# cyrf6936-bob.net
KiCad netlist of a schematic drawn in EAGLE
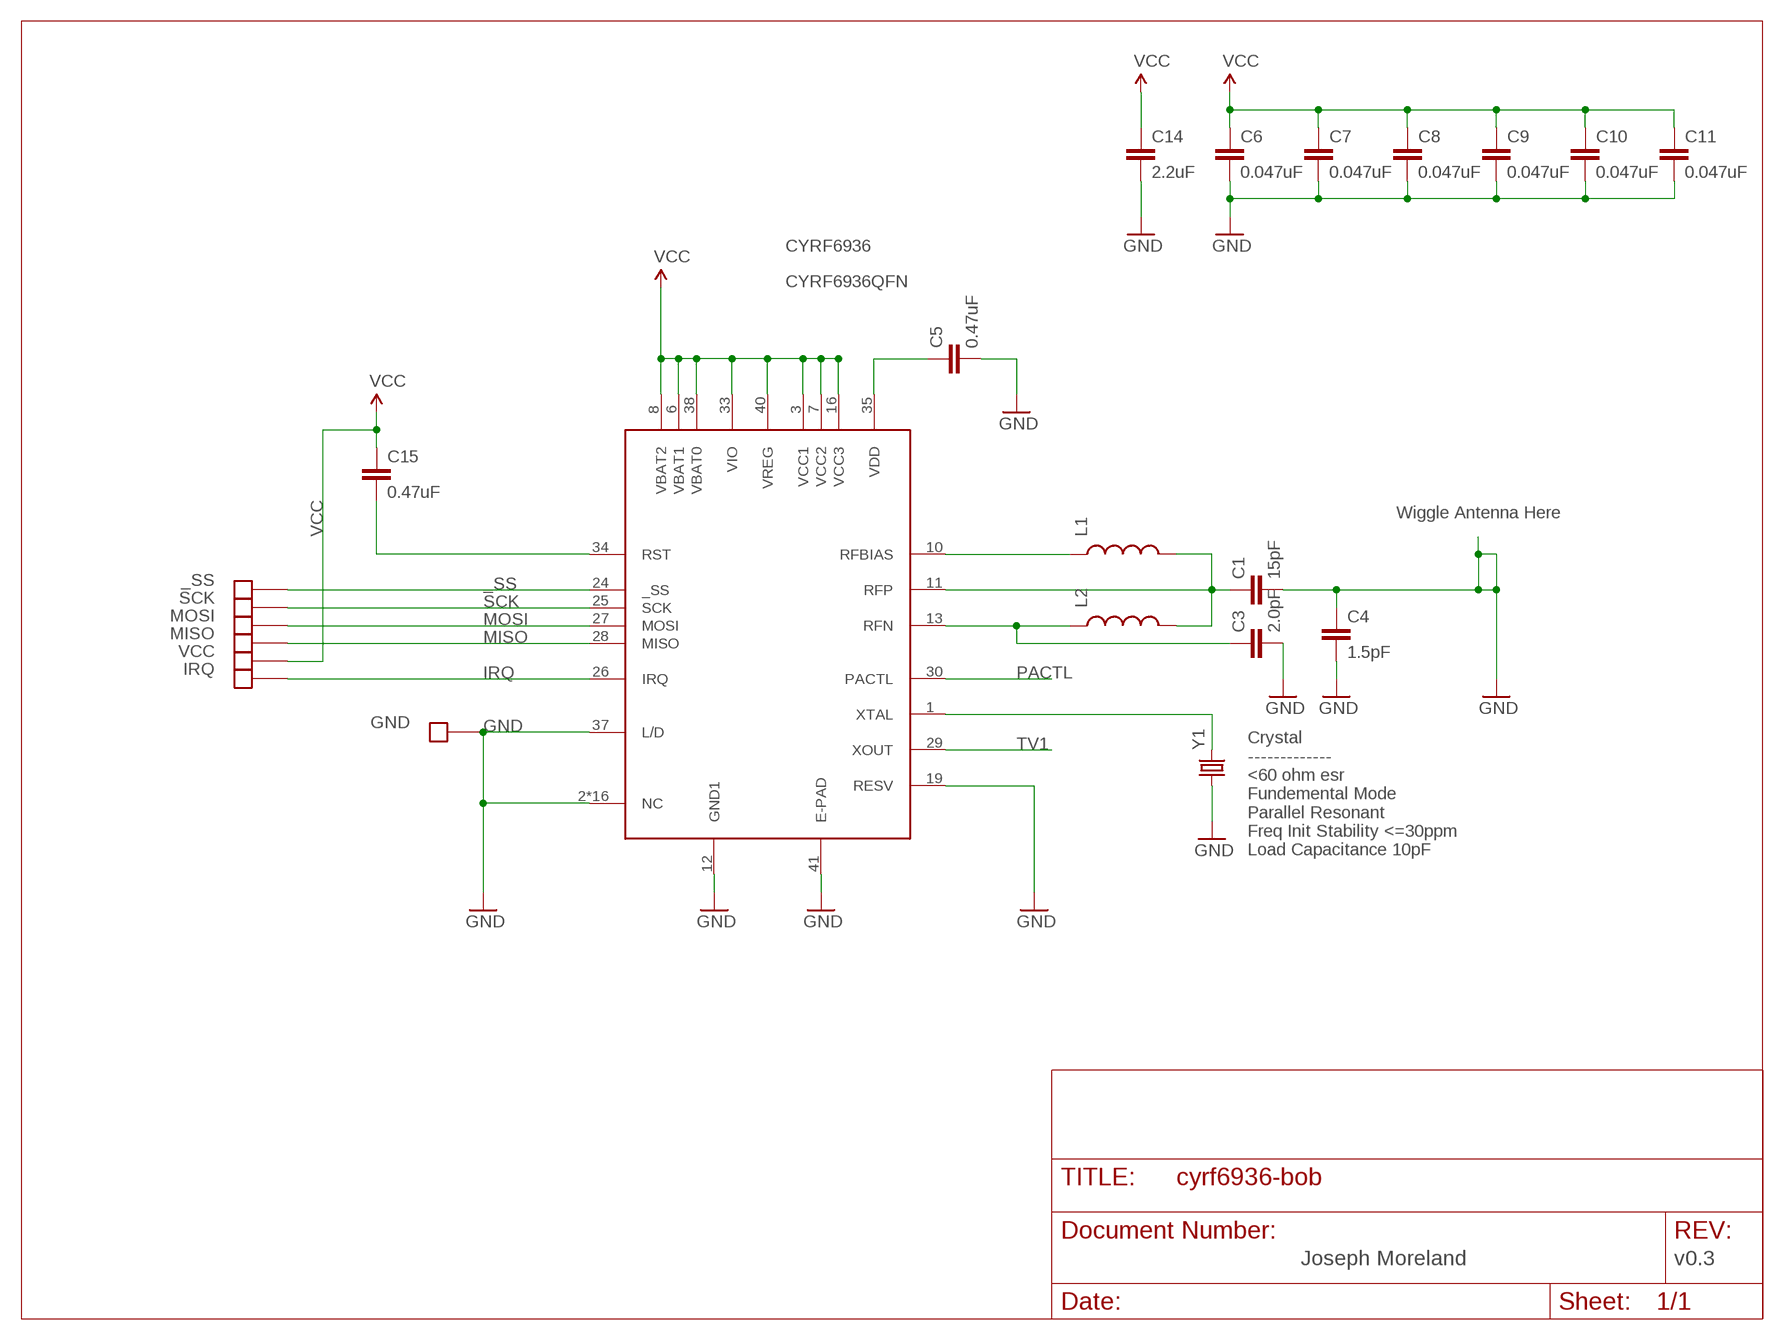
[diagram p0: schematic, sheet 1]

(export (version "E")
  (design (tool "Eeschema 10.0.6"))
  (components
    (comp (ref "C1")
      (value "15pF")
      (footprint "eagle-import:0402-CAP")
      (fields (field (name "PARTNO") "C0402C150J5GACTU"))
      (libsource (lib "eagle-import") (part "CAP0402-CAP"))
    )
    (comp (ref "C3")
      (value "2.0pF")
      (footprint "eagle-import:0402-CAP")
      (fields (field (name "PARTNO") "C0402C209C5GACTU"))
      (libsource (lib "eagle-import") (part "CAP0402-CAP"))
    )
    (comp (ref "C4")
      (value "1.5pF")
      (footprint "eagle-import:0402-CAP")
      (fields (field (name "PARTNO") "C0402C159B5GACTU"))
      (libsource (lib "eagle-import") (part "CAP0402-CAP"))
    )
    (comp (ref "C5")
      (value "0.47uF")
      (footprint "eagle-import:0402-CAP")
      (fields (field (name "PARTNO") "GRM155R60J474KE19D"))
      (libsource (lib "eagle-import") (part "CAP0402-CAP"))
    )
    (comp (ref "C6")
      (value "0.047uF")
      (footprint "eagle-import:0402-CAP")
      (fields (field (name "PARTNO") "0402YD473KAT2A"))
      (libsource (lib "eagle-import") (part "CAP0402-CAP"))
    )
    (comp (ref "C7")
      (value "0.047uF")
      (footprint "eagle-import:0402-CAP")
      (fields (field (name "PARTNO") "0402YD473KAT2A"))
      (libsource (lib "eagle-import") (part "CAP0402-CAP"))
    )
    (comp (ref "C8")
      (value "0.047uF")
      (footprint "eagle-import:0402-CAP")
      (fields (field (name "PARTNO") "0402YD473KAT2A"))
      (libsource (lib "eagle-import") (part "CAP0402-CAP"))
    )
    (comp (ref "C9")
      (value "0.047uF")
      (footprint "eagle-import:0402-CAP")
      (fields (field (name "PARTNO") "0402YD473KAT2A"))
      (libsource (lib "eagle-import") (part "CAP0402-CAP"))
    )
    (comp (ref "C10")
      (value "0.047uF")
      (footprint "eagle-import:0402-CAP")
      (fields (field (name "PARTNO") "0402YD473KAT2A"))
      (libsource (lib "eagle-import") (part "CAP0402-CAP"))
    )
    (comp (ref "C11")
      (value "0.047uF")
      (footprint "eagle-import:0402-CAP")
      (fields (field (name "PARTNO") "0402YD473KAT2A"))
      (libsource (lib "eagle-import") (part "CAP0402-CAP"))
    )
    (comp (ref "C14")
      (value "2.2uF")
      (footprint "eagle-import:0805")
      (fields (field (name "PARTNO") "GRM21BR71A225KA01L"))
      (libsource (lib "eagle-import") (part "CAP0805"))
    )
    (comp (ref "C15")
      (value "0.47uF")
      (footprint "eagle-import:0402-CAP")
      (fields (field (name "PARTNO") "GRM155R60J474KE19D"))
      (libsource (lib "eagle-import") (part "CAP0402-CAP"))
    )
    (comp (ref "CYRF6936")
      (value "CYRF6936QFN")
      (footprint "eagle-import:QFN50P600X600X90-41N")
      (fields (field (name "PARTNO") "CYRF6936B-40LTXC"))
      (libsource (lib "eagle-import") (part "CYRF6936QFN"))
    )
    (comp (ref "GND")
      (value "SOLDER_PADTH")
      (footprint "eagle-import:1X1_50MIL")
      (libsource (lib "eagle-import") (part "SOLDER_PADTH"))
    )
    (comp (ref "IRQ")
      (value "SOLDER_PADTH")
      (footprint "eagle-import:1X1_50MIL")
      (libsource (lib "eagle-import") (part "SOLDER_PADTH"))
    )
    (comp (ref "L1")
      (value "INDUCTOR0603")
      (footprint "eagle-import:0603")
      (fields (field (name "PARTNO") "ELJ-RE22NGFA"))
      (libsource (lib "eagle-import") (part "INDUCTOR0603"))
    )
    (comp (ref "L2")
      (value "INDUCTOR0402")
      (footprint "eagle-import:C0402")
      (fields (field (name "PARTNO") "ELJ-RF1N8DFB"))
      (libsource (lib "eagle-import") (part "INDUCTOR0402"))
    )
    (comp (ref "MISO")
      (value "SOLDER_PADTH")
      (footprint "eagle-import:1X1_50MIL")
      (libsource (lib "eagle-import") (part "SOLDER_PADTH"))
    )
    (comp (ref "MOSI")
      (value "SOLDER_PADTH")
      (footprint "eagle-import:1X1_50MIL")
      (libsource (lib "eagle-import") (part "SOLDER_PADTH"))
    )
    (comp (ref "SCK")
      (value "SOLDER_PADTH")
      (footprint "eagle-import:1X1_50MIL")
      (libsource (lib "eagle-import") (part "SOLDER_PADTH"))
    )
    (comp (ref "VCC")
      (value "SOLDER_PADTH")
      (footprint "eagle-import:1X1_50MIL")
      (libsource (lib "eagle-import") (part "SOLDER_PADTH"))
    )
    (comp (ref "Y1")
      (value "CRYSTAL5X3")
      (footprint "eagle-import:CRYSTAL-SMD-5X3")
      (fields (field (name "PARTNO") "7B-12.000MEEQ-T"))
      (libsource (lib "eagle-import") (part "CRYSTAL5X3"))
    )
    (comp (ref "_SS")
      (value "SOLDER_PADTH")
      (footprint "eagle-import:1X1_50MIL")
      (libsource (lib "eagle-import") (part "SOLDER_PADTH"))
    )
  )
  (nets
    (net (code "1") (name "/IRQ") (class "Default")
      (node (ref "CYRF6936") (pin "26") (pinfunction "IRQ_26") (pintype "bidirectional"))
      (node (ref "IRQ") (pin "P$1") (pinfunction "NET_P$1") (pintype "bidirectional"))
    )
    (net (code "2") (name "/MISO") (class "Default")
      (node (ref "CYRF6936") (pin "28") (pinfunction "MISO_28") (pintype "bidirectional"))
      (node (ref "MISO") (pin "P$1") (pinfunction "NET_P$1") (pintype "bidirectional"))
    )
    (net (code "3") (name "/MOSI") (class "Default")
      (node (ref "CYRF6936") (pin "27") (pinfunction "MOSI_27") (pintype "bidirectional"))
      (node (ref "MOSI") (pin "P$1") (pinfunction "NET_P$1") (pintype "bidirectional"))
    )
    (net (code "4") (name "/PACTL") (class "Default")
      (node (ref "CYRF6936") (pin "30") (pinfunction "PACTL_30") (pintype "bidirectional"))
    )
    (net (code "5") (name "/SCK") (class "Default")
      (node (ref "CYRF6936") (pin "25") (pinfunction "SCK_25") (pintype "bidirectional"))
      (node (ref "SCK") (pin "P$1") (pinfunction "NET_P$1") (pintype "bidirectional"))
    )
    (net (code "6") (name "/TV1") (class "Default")
      (node (ref "CYRF6936") (pin "29") (pinfunction "XOUT_29") (pintype "bidirectional"))
    )
    (net (code "7") (name "/_SS") (class "Default")
      (node (ref "CYRF6936") (pin "24") (pinfunction "_SS_24") (pintype "bidirectional"))
      (node (ref "_SS") (pin "P$1") (pinfunction "NET_P$1") (pintype "bidirectional"))
    )
    (net (code "8") (name "GND") (class "Default")
      (node (ref "C1") (pin "2") (pinfunction "2_2") (pintype "passive"))
      (node (ref "C10") (pin "2") (pinfunction "2_2") (pintype "passive"))
      (node (ref "C11") (pin "2") (pinfunction "2_2") (pintype "passive"))
      (node (ref "C14") (pin "2") (pinfunction "2_2") (pintype "passive"))
      (node (ref "C3") (pin "2") (pinfunction "2_2") (pintype "passive"))
      (node (ref "C4") (pin "1") (pinfunction "1_1") (pintype "passive"))
      (node (ref "C4") (pin "2") (pinfunction "2_2") (pintype "passive"))
      (node (ref "C5") (pin "2") (pinfunction "2_2") (pintype "passive"))
      (node (ref "C6") (pin "2") (pinfunction "2_2") (pintype "passive"))
      (node (ref "C7") (pin "2") (pinfunction "2_2") (pintype "passive"))
      (node (ref "C8") (pin "2") (pinfunction "2_2") (pintype "passive"))
      (node (ref "C9") (pin "2") (pinfunction "2_2") (pintype "passive"))
      (node (ref "CYRF6936") (pin "12") (pinfunction "GND1_12") (pintype "bidirectional"))
      (node (ref "CYRF6936") (pin "14") (pinfunction "NC_14") (pintype "bidirectional"))
      (node (ref "CYRF6936") (pin "15") (pinfunction "NC_15") (pintype "bidirectional"))
      (node (ref "CYRF6936") (pin "17") (pinfunction "NC_17") (pintype "bidirectional"))
      (node (ref "CYRF6936") (pin "18") (pinfunction "NC_18") (pintype "bidirectional"))
      (node (ref "CYRF6936") (pin "19") (pinfunction "RESV_19") (pintype "bidirectional"))
      (node (ref "CYRF6936") (pin "2") (pinfunction "NC_2") (pintype "bidirectional"))
      (node (ref "CYRF6936") (pin "20") (pinfunction "NC_20") (pintype "bidirectional"))
      (node (ref "CYRF6936") (pin "21") (pinfunction "NC_21") (pintype "bidirectional"))
      (node (ref "CYRF6936") (pin "22") (pinfunction "NC_22") (pintype "bidirectional"))
      (node (ref "CYRF6936") (pin "23") (pinfunction "NC_23") (pintype "bidirectional"))
      (node (ref "CYRF6936") (pin "31") (pinfunction "NC_31") (pintype "bidirectional"))
      (node (ref "CYRF6936") (pin "32") (pinfunction "NC_32") (pintype "bidirectional"))
      (node (ref "CYRF6936") (pin "36") (pinfunction "NC_36") (pintype "bidirectional"))
      (node (ref "CYRF6936") (pin "37") (pinfunction "L/D_37") (pintype "bidirectional"))
      (node (ref "CYRF6936") (pin "39") (pinfunction "NC_39") (pintype "bidirectional"))
      (node (ref "CYRF6936") (pin "4") (pinfunction "NC_4") (pintype "bidirectional"))
      (node (ref "CYRF6936") (pin "41") (pinfunction "E-PAD_41") (pintype "bidirectional"))
      (node (ref "CYRF6936") (pin "5") (pinfunction "NC_5") (pintype "bidirectional"))
      (node (ref "CYRF6936") (pin "9") (pinfunction "NC_9") (pintype "bidirectional"))
      (node (ref "GND") (pin "P$1") (pinfunction "NET_P$1") (pintype "bidirectional"))
      (node (ref "Y1") (pin "1") (pinfunction "1_1") (pintype "passive"))
    )
    (net (code "9") (name "Net-(CYRF6936-RFBIAS)") (class "Default")
      (node (ref "CYRF6936") (pin "10") (pinfunction "RFBIAS_10") (pintype "bidirectional"))
      (node (ref "L1") (pin "1") (pinfunction "1_1") (pintype "passive"))
    )
    (net (code "10") (name "Net-(CYRF6936-RFN)") (class "Default")
      (node (ref "C3") (pin "1") (pinfunction "1_1") (pintype "passive"))
      (node (ref "CYRF6936") (pin "13") (pinfunction "RFN_13") (pintype "bidirectional"))
      (node (ref "L2") (pin "1") (pinfunction "1_1") (pintype "passive"))
    )
    (net (code "11") (name "Net-(CYRF6936-RFP)") (class "Default")
      (node (ref "C1") (pin "1") (pinfunction "1_1") (pintype "passive"))
      (node (ref "CYRF6936") (pin "11") (pinfunction "RFP_11") (pintype "bidirectional"))
      (node (ref "L1") (pin "2") (pinfunction "2_2") (pintype "passive"))
      (node (ref "L2") (pin "2") (pinfunction "2_2") (pintype "passive"))
    )
    (net (code "12") (name "Net-(CYRF6936-RST)") (class "Default")
      (node (ref "C15") (pin "2") (pinfunction "2_2") (pintype "passive"))
      (node (ref "CYRF6936") (pin "34") (pinfunction "RST_34") (pintype "bidirectional"))
    )
    (net (code "13") (name "Net-(CYRF6936-VDD)") (class "Default")
      (node (ref "C5") (pin "1") (pinfunction "1_1") (pintype "passive"))
      (node (ref "CYRF6936") (pin "35") (pinfunction "VDD_35") (pintype "bidirectional"))
    )
    (net (code "14") (name "Net-(CYRF6936-XTAL)") (class "Default")
      (node (ref "CYRF6936") (pin "1") (pinfunction "XTAL_1") (pintype "bidirectional"))
      (node (ref "Y1") (pin "3") (pinfunction "2_3") (pintype "passive"))
    )
    (net (code "15") (name "VCC") (class "Default")
      (node (ref "C10") (pin "1") (pinfunction "1_1") (pintype "passive"))
      (node (ref "C11") (pin "1") (pinfunction "1_1") (pintype "passive"))
      (node (ref "C14") (pin "1") (pinfunction "1_1") (pintype "passive"))
      (node (ref "C15") (pin "1") (pinfunction "1_1") (pintype "passive"))
      (node (ref "C6") (pin "1") (pinfunction "1_1") (pintype "passive"))
      (node (ref "C7") (pin "1") (pinfunction "1_1") (pintype "passive"))
      (node (ref "C8") (pin "1") (pinfunction "1_1") (pintype "passive"))
      (node (ref "C9") (pin "1") (pinfunction "1_1") (pintype "passive"))
      (node (ref "CYRF6936") (pin "16") (pinfunction "VCC3_16") (pintype "bidirectional"))
      (node (ref "CYRF6936") (pin "3") (pinfunction "VCC1_3") (pintype "bidirectional"))
      (node (ref "CYRF6936") (pin "33") (pinfunction "VIO_33") (pintype "bidirectional"))
      (node (ref "CYRF6936") (pin "38") (pinfunction "VBAT0_38") (pintype "bidirectional"))
      (node (ref "CYRF6936") (pin "40") (pinfunction "VREG_40") (pintype "bidirectional"))
      (node (ref "CYRF6936") (pin "6") (pinfunction "VBAT1_6") (pintype "bidirectional"))
      (node (ref "CYRF6936") (pin "7") (pinfunction "VCC2_7") (pintype "bidirectional"))
      (node (ref "CYRF6936") (pin "8") (pinfunction "VBAT2_8") (pintype "bidirectional"))
      (node (ref "VCC") (pin "P$1") (pinfunction "NET_P$1") (pintype "bidirectional"))
    )
  )
)
